# Qwiic_Long_Distance-PCA9615.net
KiCad netlist of a schematic drawn in EAGLE
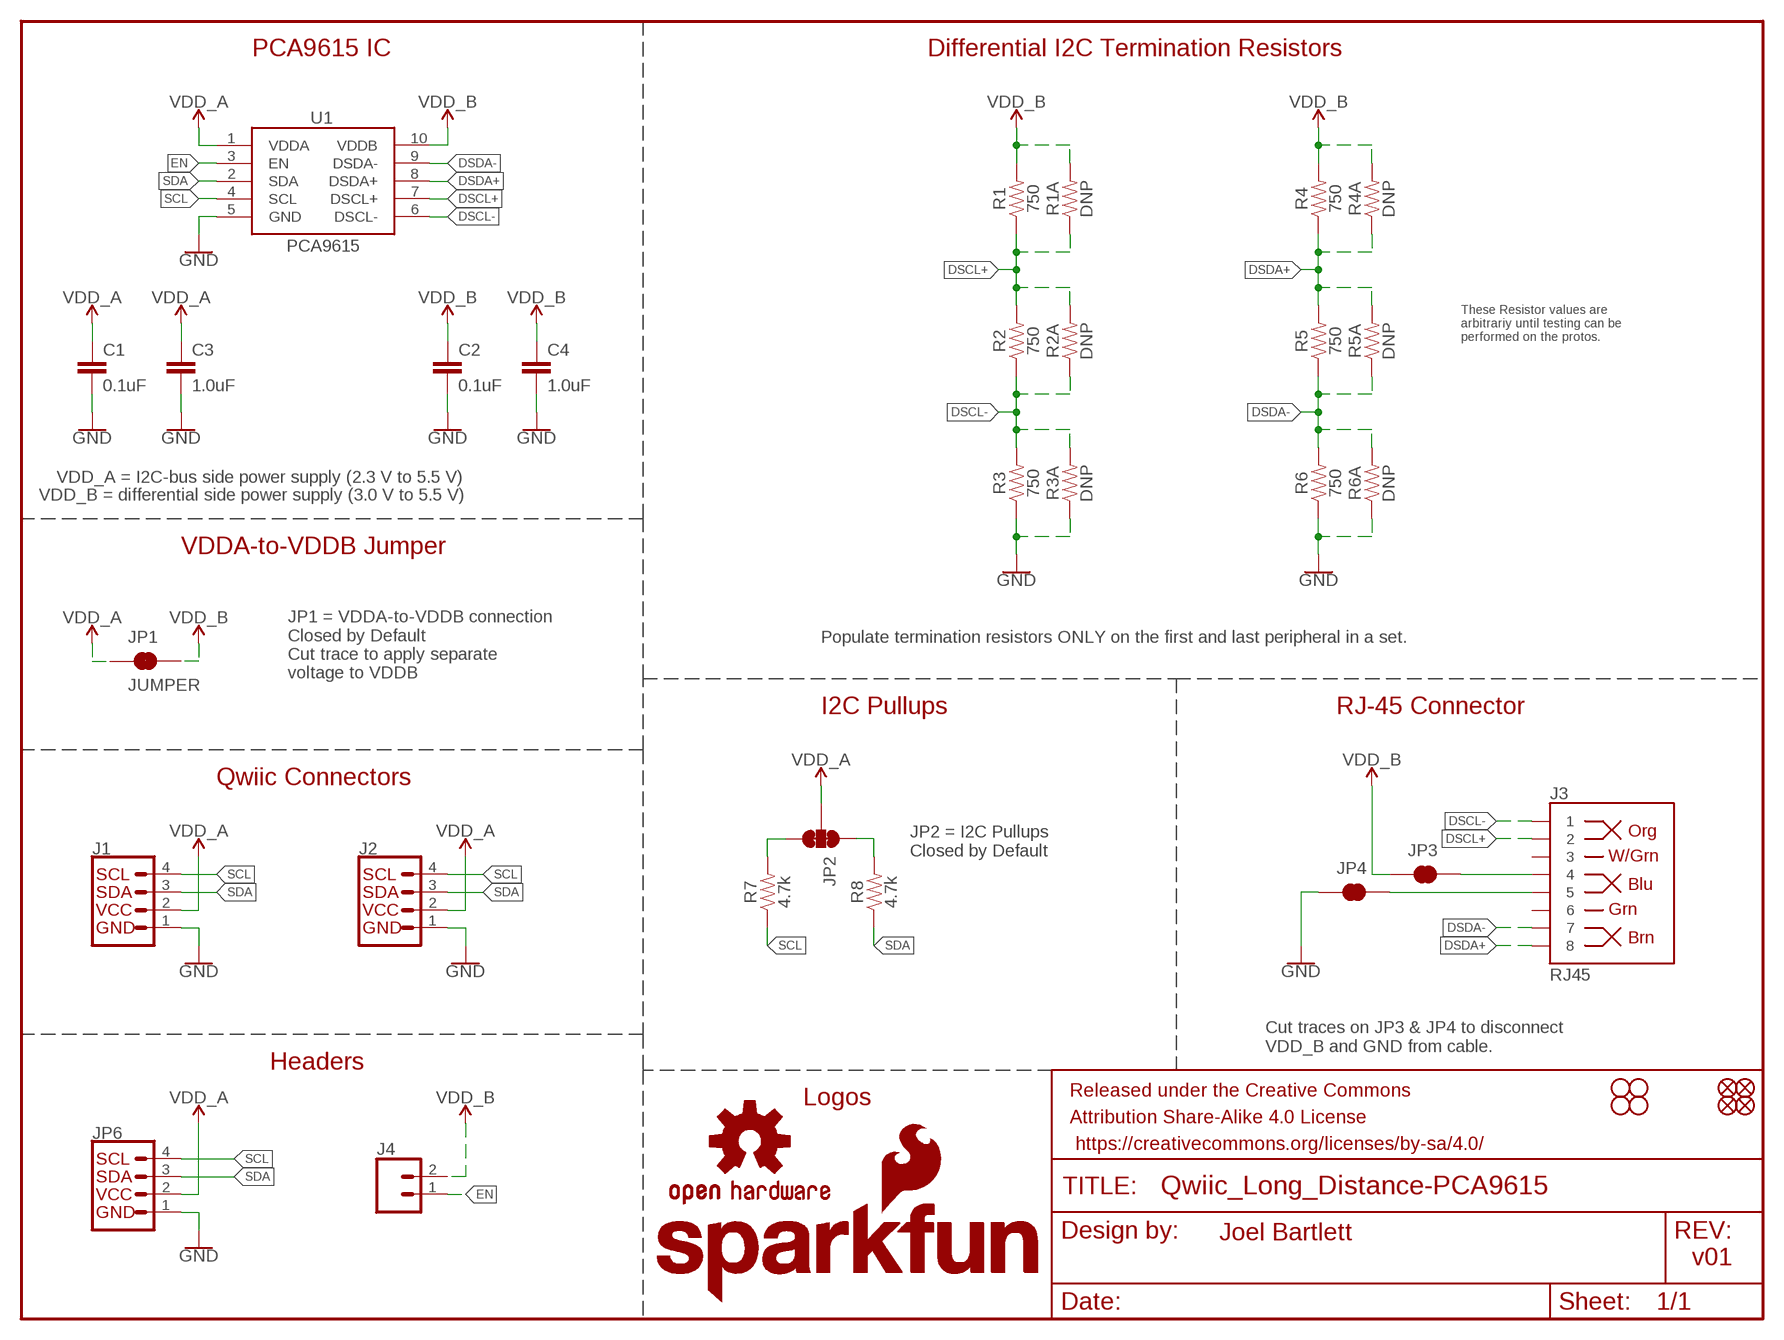
[diagram p0: schematic, sheet 1]

(export (version "E")
  (design (tool "Eeschema 10.0.6"))
  (components
    (comp (ref "C1")
      (value "0.1uF")
      (footprint "eagle-import:0603")
      (libsource (lib "eagle-import") (part "0.1UF-0603-25V-(+80/-20%)"))
    )
    (comp (ref "C2")
      (value "0.1uF")
      (footprint "eagle-import:0603")
      (libsource (lib "eagle-import") (part "0.1UF-0603-25V-(+80/-20%)"))
    )
    (comp (ref "C3")
      (value "1.0uF")
      (footprint "eagle-import:0603")
      (libsource (lib "eagle-import") (part "1.0UF-0603-16V-10%"))
    )
    (comp (ref "C4")
      (value "1.0uF")
      (footprint "eagle-import:0603")
      (libsource (lib "eagle-import") (part "1.0UF-0603-16V-10%"))
    )
    (comp (ref "FD1")
      (value "FIDUCIALUFIDUCIAL")
      (footprint "eagle-import:FIDUCIAL-MICRO")
      (libsource (lib "eagle-import") (part "FIDUCIALUFIDUCIAL"))
    )
    (comp (ref "FD2")
      (value "FIDUCIALUFIDUCIAL")
      (footprint "eagle-import:FIDUCIAL-MICRO")
      (libsource (lib "eagle-import") (part "FIDUCIALUFIDUCIAL"))
    )
    (comp (ref "FD3")
      (value "FIDUCIALUFIDUCIAL")
      (footprint "eagle-import:FIDUCIAL-MICRO")
      (libsource (lib "eagle-import") (part "FIDUCIALUFIDUCIAL"))
    )
    (comp (ref "FD4")
      (value "FIDUCIALUFIDUCIAL")
      (footprint "eagle-import:FIDUCIAL-MICRO")
      (libsource (lib "eagle-import") (part "FIDUCIALUFIDUCIAL"))
    )
    (comp (ref "FRAME1")
      (value "FRAME-LETTER")
      (footprint "eagle-import:CREATIVE_COMMONS")
      (libsource (lib "eagle-import") (part "FRAME-LETTER"))
    )
    (comp (ref "H1")
      (value "STAND-OFF")
      (footprint "eagle-import:STAND-OFF")
      (libsource (lib "eagle-import") (part "STAND-OFF"))
    )
    (comp (ref "H2")
      (value "STAND-OFF")
      (footprint "eagle-import:STAND-OFF")
      (libsource (lib "eagle-import") (part "STAND-OFF"))
    )
    (comp (ref "H3")
      (value "STAND-OFF")
      (footprint "eagle-import:STAND-OFF")
      (libsource (lib "eagle-import") (part "STAND-OFF"))
    )
    (comp (ref "H4")
      (value "STAND-OFF")
      (footprint "eagle-import:STAND-OFF")
      (libsource (lib "eagle-import") (part "STAND-OFF"))
    )
    (comp (ref "J1")
      (value "QWIIC_CONNECTORJS-1MM")
      (footprint "eagle-import:1X04_1MM_RA")
      (libsource (lib "eagle-import") (part "QWIIC_CONNECTORJS-1MM"))
    )
    (comp (ref "J2")
      (value "QWIIC_CONNECTORJS-1MM")
      (footprint "eagle-import:1X04_1MM_RA")
      (libsource (lib "eagle-import") (part "QWIIC_CONNECTORJS-1MM"))
    )
    (comp (ref "J3")
      (value "RJ45")
      (footprint "eagle-import:RJ45-8")
      (libsource (lib "eagle-import") (part "RJ45-8"))
    )
    (comp (ref "J4")
      (value "CONN_02")
      (footprint "eagle-import:1X02")
      (libsource (lib "eagle-import") (part "CONN_02"))
    )
    (comp (ref "JP1")
      (value "JUMPER")
      (footprint "eagle-import:SMT-JUMPER_2_NC_TRACE_SILK")
      (libsource (lib "eagle-import") (part "JUMPER-SMT_2_NC_TRACE_SILK"))
    )
    (comp (ref "JP2")
      (value "JUMPER-SMT_3_2-NC_TRACE_SILK")
      (footprint "eagle-import:SMT-JUMPER_3_2-NC_TRACE_SILK")
      (libsource (lib "eagle-import") (part "JUMPER-SMT_3_2-NC_TRACE_SILK"))
    )
    (comp (ref "JP3")
      (value "JUMPER-SMT_2_NC_TRACE_SILK")
      (footprint "eagle-import:SMT-JUMPER_2_NC_TRACE_SILK")
      (libsource (lib "eagle-import") (part "JUMPER-SMT_2_NC_TRACE_SILK"))
    )
    (comp (ref "JP4")
      (value "JUMPER-SMT_2_NC_TRACE_SILK")
      (footprint "eagle-import:SMT-JUMPER_2_NC_TRACE_SILK")
      (libsource (lib "eagle-import") (part "JUMPER-SMT_2_NC_TRACE_SILK"))
    )
    (comp (ref "JP6")
      (value "I2C_STANDARDSILK")
      (footprint "eagle-import:1X04")
      (libsource (lib "eagle-import") (part "I2C_STANDARDSILK"))
    )
    (comp (ref "LOGO1")
      (value "OSHW-LOGOM")
      (footprint "eagle-import:OSHW-LOGO-M")
      (libsource (lib "eagle-import") (part "OSHW-LOGOM"))
    )
    (comp (ref "LOGO2")
      (value "SFE_LOGO_NAME.1_INCH")
      (footprint "eagle-import:SFE_LOGO_NAME_.1")
      (libsource (lib "eagle-import") (part "SFE_LOGO_NAME.1_INCH"))
    )
    (comp (ref "LOGO5")
      (value "SFE_LOGO_NAME_FLAME.1_INCH")
      (footprint "eagle-import:SFE_LOGO_NAME_FLAME_.1")
      (libsource (lib "eagle-import") (part "SFE_LOGO_NAME_FLAME.1_INCH"))
    )
    (comp (ref "R1")
      (value "750")
      (footprint "eagle-import:0603")
      (libsource (lib "eagle-import") (part "750OHM-0603-1/10W-1%"))
    )
    (comp (ref "R1A")
      (value "DNP")
      (footprint "eagle-import:AXIAL-0.3")
      (libsource (lib "eagle-import") (part "RESISTORAXIAL-0.3"))
    )
    (comp (ref "R2")
      (value "750")
      (footprint "eagle-import:0603")
      (libsource (lib "eagle-import") (part "750OHM-0603-1/10W-1%"))
    )
    (comp (ref "R2A")
      (value "DNP")
      (footprint "eagle-import:AXIAL-0.3")
      (libsource (lib "eagle-import") (part "RESISTORAXIAL-0.3"))
    )
    (comp (ref "R3")
      (value "750")
      (footprint "eagle-import:0603")
      (libsource (lib "eagle-import") (part "750OHM-0603-1/10W-1%"))
    )
    (comp (ref "R3A")
      (value "DNP")
      (footprint "eagle-import:AXIAL-0.3")
      (libsource (lib "eagle-import") (part "RESISTORAXIAL-0.3"))
    )
    (comp (ref "R4")
      (value "750")
      (footprint "eagle-import:0603")
      (libsource (lib "eagle-import") (part "750OHM-0603-1/10W-1%"))
    )
    (comp (ref "R4A")
      (value "DNP")
      (footprint "eagle-import:AXIAL-0.3")
      (libsource (lib "eagle-import") (part "RESISTORAXIAL-0.3"))
    )
    (comp (ref "R5")
      (value "750")
      (footprint "eagle-import:0603")
      (libsource (lib "eagle-import") (part "750OHM-0603-1/10W-1%"))
    )
    (comp (ref "R5A")
      (value "DNP")
      (footprint "eagle-import:AXIAL-0.3")
      (libsource (lib "eagle-import") (part "RESISTORAXIAL-0.3"))
    )
    (comp (ref "R6")
      (value "750")
      (footprint "eagle-import:0603")
      (libsource (lib "eagle-import") (part "750OHM-0603-1/10W-1%"))
    )
    (comp (ref "R6A")
      (value "DNP")
      (footprint "eagle-import:AXIAL-0.3")
      (libsource (lib "eagle-import") (part "RESISTORAXIAL-0.3"))
    )
    (comp (ref "R7")
      (value "4.7k")
      (footprint "eagle-import:0603")
      (libsource (lib "eagle-import") (part "4.7KOHM-0603-1/10W-1%"))
    )
    (comp (ref "R8")
      (value "4.7k")
      (footprint "eagle-import:0603")
      (libsource (lib "eagle-import") (part "4.7KOHM-0603-1/10W-1%"))
    )
    (comp (ref "U1")
      (value "PCA9615")
      (footprint "eagle-import:TSSOP10")
      (libsource (lib "eagle-import") (part "PCA9615"))
    )
  )
  (nets
    (net (code "1") (name "DSCL+") (class "Default")
      (node (ref "J3") (pin "2") (pinfunction "2_2") (pintype "bidirectional"))
      (node (ref "R1") (pin "1") (pinfunction "1_1") (pintype "passive"))
      (node (ref "R1A") (pin "P$1") (pinfunction "1_P$1") (pintype "passive"))
      (node (ref "R2") (pin "2") (pinfunction "2_2") (pintype "passive"))
      (node (ref "R2A") (pin "P$2") (pinfunction "2_P$2") (pintype "passive"))
      (node (ref "U1") (pin "7") (pinfunction "DSCL+_7") (pintype "bidirectional"))
    )
    (net (code "2") (name "DSCL-") (class "Default")
      (node (ref "J3") (pin "1") (pinfunction "1_1") (pintype "bidirectional"))
      (node (ref "R2") (pin "1") (pinfunction "1_1") (pintype "passive"))
      (node (ref "R2A") (pin "P$1") (pinfunction "1_P$1") (pintype "passive"))
      (node (ref "R3") (pin "2") (pinfunction "2_2") (pintype "passive"))
      (node (ref "R3A") (pin "P$2") (pinfunction "2_P$2") (pintype "passive"))
      (node (ref "U1") (pin "6") (pinfunction "DSCL-_6") (pintype "bidirectional"))
    )
    (net (code "3") (name "DSDA+") (class "Default")
      (node (ref "J3") (pin "8") (pinfunction "8_8") (pintype "bidirectional"))
      (node (ref "R4") (pin "1") (pinfunction "1_1") (pintype "passive"))
      (node (ref "R4A") (pin "P$1") (pinfunction "1_P$1") (pintype "passive"))
      (node (ref "R5") (pin "2") (pinfunction "2_2") (pintype "passive"))
      (node (ref "R5A") (pin "P$2") (pinfunction "2_P$2") (pintype "passive"))
      (node (ref "U1") (pin "8") (pinfunction "DSDA+_8") (pintype "bidirectional"))
    )
    (net (code "4") (name "DSDA-") (class "Default")
      (node (ref "J3") (pin "7") (pinfunction "7_7") (pintype "bidirectional"))
      (node (ref "R5") (pin "1") (pinfunction "1_1") (pintype "passive"))
      (node (ref "R5A") (pin "P$1") (pinfunction "1_P$1") (pintype "passive"))
      (node (ref "R6") (pin "2") (pinfunction "2_2") (pintype "passive"))
      (node (ref "R6A") (pin "P$2") (pinfunction "2_P$2") (pintype "passive"))
      (node (ref "U1") (pin "9") (pinfunction "DSDA-_9") (pintype "bidirectional"))
    )
    (net (code "5") (name "EN") (class "Default")
      (node (ref "J4") (pin "1") (pinfunction "1_1") (pintype "passive"))
      (node (ref "U1") (pin "3") (pinfunction "EN_3") (pintype "bidirectional"))
    )
    (net (code "6") (name "GND") (class "Default")
      (node (ref "C1") (pin "2") (pinfunction "2_2") (pintype "passive"))
      (node (ref "C2") (pin "2") (pinfunction "2_2") (pintype "passive"))
      (node (ref "C3") (pin "2") (pinfunction "2_2") (pintype "passive"))
      (node (ref "C4") (pin "2") (pinfunction "2_2") (pintype "passive"))
      (node (ref "J1") (pin "1") (pinfunction "1_1") (pintype "power_in"))
      (node (ref "J2") (pin "1") (pinfunction "1_1") (pintype "power_in"))
      (node (ref "JP4") (pin "1") (pinfunction "1_1") (pintype "passive"))
      (node (ref "JP6") (pin "1") (pinfunction "GND_1") (pintype "power_in"))
      (node (ref "R3") (pin "1") (pinfunction "1_1") (pintype "passive"))
      (node (ref "R3A") (pin "P$1") (pinfunction "1_P$1") (pintype "passive"))
      (node (ref "R6") (pin "1") (pinfunction "1_1") (pintype "passive"))
      (node (ref "R6A") (pin "P$1") (pinfunction "1_P$1") (pintype "passive"))
      (node (ref "U1") (pin "5") (pinfunction "GND_5") (pintype "bidirectional"))
    )
    (net (code "7") (name "Net-(J3-Pad4)") (class "Default")
      (node (ref "J3") (pin "4") (pinfunction "4_4") (pintype "bidirectional"))
      (node (ref "JP3") (pin "2") (pinfunction "2_2") (pintype "passive"))
    )
    (net (code "8") (name "Net-(J3-Pad5)") (class "Default")
      (node (ref "J3") (pin "5") (pinfunction "5_5") (pintype "bidirectional"))
      (node (ref "JP4") (pin "2") (pinfunction "2_2") (pintype "passive"))
    )
    (net (code "9") (name "Net-(JP2-Pad1)") (class "Default")
      (node (ref "JP2") (pin "1") (pinfunction "1_1") (pintype "passive"))
      (node (ref "R8") (pin "2") (pinfunction "2_2") (pintype "passive"))
    )
    (net (code "10") (name "Net-(JP2-Pad3)") (class "Default")
      (node (ref "JP2") (pin "3") (pinfunction "3_3") (pintype "passive"))
      (node (ref "R7") (pin "2") (pinfunction "2_2") (pintype "passive"))
    )
    (net (code "11") (name "SCL") (class "Default")
      (node (ref "J1") (pin "4") (pinfunction "4_4") (pintype "passive"))
      (node (ref "J2") (pin "4") (pinfunction "4_4") (pintype "passive"))
      (node (ref "JP6") (pin "4") (pinfunction "SCL_4") (pintype "passive"))
      (node (ref "R7") (pin "1") (pinfunction "1_1") (pintype "passive"))
      (node (ref "U1") (pin "4") (pinfunction "SCL_4") (pintype "bidirectional"))
    )
    (net (code "12") (name "SDA") (class "Default")
      (node (ref "J1") (pin "3") (pinfunction "3_3") (pintype "passive"))
      (node (ref "J2") (pin "3") (pinfunction "3_3") (pintype "passive"))
      (node (ref "JP6") (pin "3") (pinfunction "SDA_3") (pintype "passive"))
      (node (ref "R8") (pin "1") (pinfunction "1_1") (pintype "passive"))
      (node (ref "U1") (pin "2") (pinfunction "SDA_2") (pintype "bidirectional"))
    )
    (net (code "13") (name "VDD_A") (class "Default")
      (node (ref "C1") (pin "1") (pinfunction "1_1") (pintype "passive"))
      (node (ref "C3") (pin "1") (pinfunction "1_1") (pintype "passive"))
      (node (ref "J1") (pin "2") (pinfunction "2_2") (pintype "power_in"))
      (node (ref "J2") (pin "2") (pinfunction "2_2") (pintype "power_in"))
      (node (ref "JP1") (pin "1") (pinfunction "1_1") (pintype "passive"))
      (node (ref "JP2") (pin "2") (pinfunction "2_2") (pintype "passive"))
      (node (ref "JP6") (pin "2") (pinfunction "VCC_2") (pintype "power_in"))
      (node (ref "U1") (pin "1") (pinfunction "VDDA_1") (pintype "bidirectional"))
    )
    (net (code "14") (name "VDD_B") (class "Default")
      (node (ref "C2") (pin "1") (pinfunction "1_1") (pintype "passive"))
      (node (ref "C4") (pin "1") (pinfunction "1_1") (pintype "passive"))
      (node (ref "J4") (pin "2") (pinfunction "2_2") (pintype "passive"))
      (node (ref "JP1") (pin "2") (pinfunction "2_2") (pintype "passive"))
      (node (ref "JP3") (pin "1") (pinfunction "1_1") (pintype "passive"))
      (node (ref "R1") (pin "2") (pinfunction "2_2") (pintype "passive"))
      (node (ref "R1A") (pin "P$2") (pinfunction "2_P$2") (pintype "passive"))
      (node (ref "R4") (pin "2") (pinfunction "2_2") (pintype "passive"))
      (node (ref "R4A") (pin "P$2") (pinfunction "2_P$2") (pintype "passive"))
      (node (ref "U1") (pin "10") (pinfunction "VDDB_10") (pintype "bidirectional"))
    )
    (net (code "15") (name "unconnected-(J3-Pad3)") (class "Default")
      (node (ref "J3") (pin "3") (pinfunction "3_3") (pintype "bidirectional"))
    )
    (net (code "16") (name "unconnected-(J3-Pad6)") (class "Default")
      (node (ref "J3") (pin "6") (pinfunction "6_6") (pintype "bidirectional"))
    )
  )
)
